# MINI_SAM_D51_012.net
KiCad netlist of a schematic drawn in EAGLE
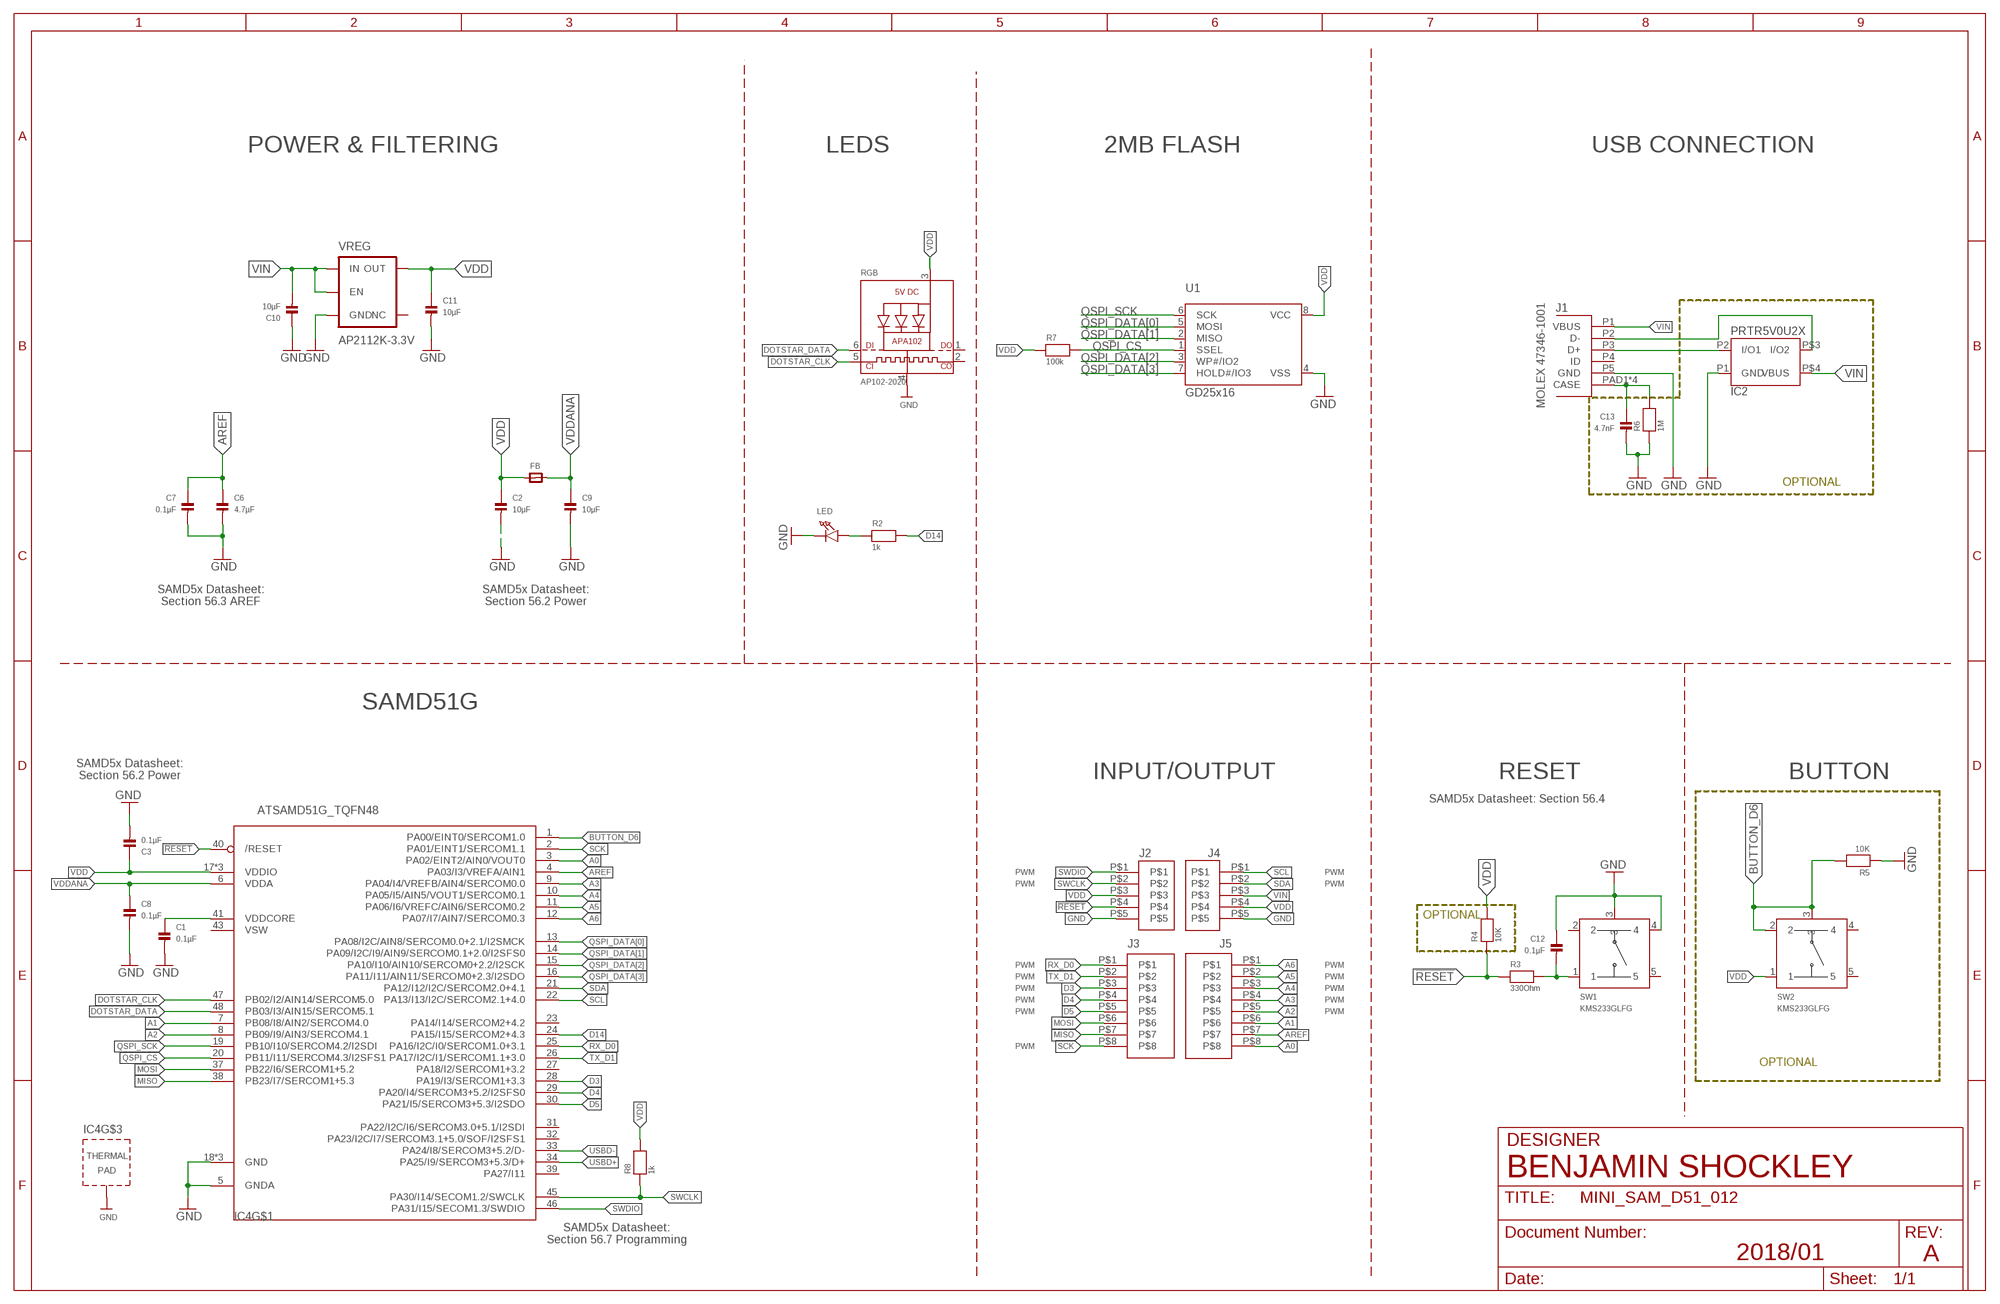
[diagram p0: schematic, sheet 1]

(export (version "E")
  (design (tool "Eeschema 10.0.6"))
  (components
    (comp (ref "C1")
      (value "0.1µF")
      (footprint "eagle-import:_0603MP")
      (libsource (lib "eagle-import") (part "CAP_CERAMIC_0603MP"))
    )
    (comp (ref "C2")
      (value "10µF")
      (footprint "eagle-import:_0603MP")
      (libsource (lib "eagle-import") (part "CAP_CERAMIC_0603MP"))
    )
    (comp (ref "C3")
      (value "0.1µF")
      (footprint "eagle-import:_0603MP")
      (libsource (lib "eagle-import") (part "CAP_CERAMIC_0603MP"))
    )
    (comp (ref "C6")
      (value "4.7µF")
      (footprint "eagle-import:_0603MP")
      (libsource (lib "eagle-import") (part "CAP_CERAMIC_0603MP"))
    )
    (comp (ref "C7")
      (value "0.1µF")
      (footprint "eagle-import:_0603MP")
      (libsource (lib "eagle-import") (part "CAP_CERAMIC_0603MP"))
    )
    (comp (ref "C8")
      (value "0.1µF")
      (footprint "eagle-import:_0603MP")
      (libsource (lib "eagle-import") (part "CAP_CERAMIC_0603MP"))
    )
    (comp (ref "C9")
      (value "10µF")
      (footprint "eagle-import:_0603MP")
      (libsource (lib "eagle-import") (part "CAP_CERAMIC_0603MP"))
    )
    (comp (ref "C10")
      (value "10µF")
      (footprint "eagle-import:_0603MP")
      (libsource (lib "eagle-import") (part "CAP_CERAMIC_0603MP"))
    )
    (comp (ref "C11")
      (value "10µF")
      (footprint "eagle-import:_0603MP")
      (libsource (lib "eagle-import") (part "CAP_CERAMIC_0603MP"))
    )
    (comp (ref "C12")
      (value "0.1µF")
      (footprint "eagle-import:_0603MP")
      (libsource (lib "eagle-import") (part "CAP_CERAMIC_0603MP"))
    )
    (comp (ref "C13")
      (value "4.7nF")
      (footprint "eagle-import:_0603MP")
      (libsource (lib "eagle-import") (part "CAP_CERAMIC_0603MP"))
    )
    (comp (ref "FB")
      (value "FERRITE_0603MP")
      (footprint "eagle-import:_0603MP")
      (libsource (lib "eagle-import") (part "FERRITE_0603MP"))
    )
    (comp (ref "IC2")
      (value "PRTR5V0U2X")
      (footprint "eagle-import:SOT143B_REFLOW")
      (libsource (lib "eagle-import") (part "PRTR5V0U2X"))
    )
    (comp (ref "IC4")
      (value "ATSAMD51G_TQFN48")
      (footprint "eagle-import:TQFN48_7MM")
      (libsource (lib "eagle-import") (part "ATSAMD51G_TQFN48"))
    )
    (comp (ref "J1")
      (value "MOLEX_47346-100147346")
      (footprint "eagle-import:MOLEX_47346-1001")
      (libsource (lib "eagle-import") (part "MOLEX_47346-100147346"))
    )
    (comp (ref "J2")
      (value "1X5_HEADER_1.27MM")
      (footprint "eagle-import:1X5_HEADER_1.27MM")
      (libsource (lib "eagle-import") (part "1X5_HEADER_1.27MM"))
    )
    (comp (ref "J3")
      (value "1X8_HEADER_1.27MM")
      (footprint "eagle-import:1X8_HEADER_1.27MM")
      (libsource (lib "eagle-import") (part "1X8_HEADER_1.27MM"))
    )
    (comp (ref "J4")
      (value "1X5_HEADER_1.27MM")
      (footprint "eagle-import:1X5_HEADER_1.27MM")
      (libsource (lib "eagle-import") (part "1X5_HEADER_1.27MM"))
    )
    (comp (ref "J5")
      (value "1X8_HEADER_1.27MM")
      (footprint "eagle-import:1X8_HEADER_1.27MM")
      (libsource (lib "eagle-import") (part "1X8_HEADER_1.27MM"))
    )
    (comp (ref "LED")
      (value "LED0805_NOOUTLINE")
      (footprint "eagle-import:CHIPLED_0805_NOOUTLINE")
      (libsource (lib "eagle-import") (part "LED0805_NOOUTLINE"))
    )
    (comp (ref "R2")
      (value "1k")
      (footprint "eagle-import:_0603MP")
      (libsource (lib "eagle-import") (part "RESISTOR_0603MP"))
    )
    (comp (ref "R3")
      (value "330Ohm")
      (footprint "eagle-import:_0603MP")
      (libsource (lib "eagle-import") (part "RESISTOR_0603MP"))
    )
    (comp (ref "R4")
      (value "10K")
      (footprint "eagle-import:_0603MP")
      (libsource (lib "eagle-import") (part "RESISTOR_0603MP"))
    )
    (comp (ref "R5")
      (value "10K")
      (footprint "eagle-import:_0603MP")
      (libsource (lib "eagle-import") (part "RESISTOR_0603MP"))
    )
    (comp (ref "R6")
      (value "1M")
      (footprint "eagle-import:_0603MP")
      (libsource (lib "eagle-import") (part "RESISTOR_0603MP"))
    )
    (comp (ref "R7")
      (value "100k")
      (footprint "eagle-import:_0603MP")
      (libsource (lib "eagle-import") (part "RESISTOR_0603MP"))
    )
    (comp (ref "R8")
      (value "1k")
      (footprint "eagle-import:_0603MP")
      (libsource (lib "eagle-import") (part "RESISTOR_0603MP"))
    )
    (comp (ref "RGB")
      (value "AP102-2020")
      (footprint "eagle-import:APA102_2020")
      (libsource (lib "eagle-import") (part "APA1022020"))
    )
    (comp (ref "SW1")
      (value "KMS233GLFG")
      (footprint "eagle-import:KMS_SWITCH")
      (libsource (lib "eagle-import") (part "KMS_SWITCHKMS"))
    )
    (comp (ref "SW2")
      (value "KMS233GLFG")
      (footprint "eagle-import:KMS_SWITCH")
      (libsource (lib "eagle-import") (part "KMS_SWITCHKMS"))
    )
    (comp (ref "U1")
      (value "GD25x16")
      (footprint "eagle-import:USON8")
      (libsource (lib "eagle-import") (part "SPIFLASH_8PINUX"))
    )
    (comp (ref "VREG")
      (value "AP2112K-3.3V")
      (footprint "eagle-import:SOT23-5")
      (libsource (lib "eagle-import") (part "V_REG_AP2112K-3.3V"))
    )
  )
  (nets
    (net (code "1") (name "/VSW") (class "Default")
      (node (ref "IC4") (pin "43") (pinfunction "VSW_43") (pintype "power_in"))
    )
    (net (code "2") (name "/~{RESET}") (class "Default")
      (node (ref "IC4") (pin "40") (pinfunction "/RESET_40") (pintype "bidirectional"))
      (node (ref "J2") (pin "P$4") (pinfunction "P$4_P$4") (pintype "bidirectional"))
      (node (ref "R3") (pin "1") (pinfunction "1_1") (pintype "passive"))
      (node (ref "R4") (pin "1") (pinfunction "1_1") (pintype "passive"))
    )
    (net (code "3") (name "A0") (class "Default")
      (node (ref "IC4") (pin "3") (pinfunction "PA02/EINT2/AIN0/VOUT0_3") (pintype "bidirectional"))
      (node (ref "J5") (pin "P$8") (pinfunction "P$8_P$8") (pintype "bidirectional"))
    )
    (net (code "4") (name "A1") (class "Default")
      (node (ref "IC4") (pin "7") (pinfunction "PB08/I8/AIN2/SERCOM4.0_7") (pintype "bidirectional"))
      (node (ref "J5") (pin "P$6") (pinfunction "P$6_P$6") (pintype "bidirectional"))
    )
    (net (code "5") (name "A2") (class "Default")
      (node (ref "IC4") (pin "8") (pinfunction "PB09/I9/AIN3/SERCOM4.1_8") (pintype "bidirectional"))
      (node (ref "J5") (pin "P$5") (pinfunction "P$5_P$5") (pintype "bidirectional"))
    )
    (net (code "6") (name "A3") (class "Default")
      (node (ref "IC4") (pin "9") (pinfunction "PA04/I4/VREFB/AIN4/SERCOM0.0_9") (pintype "bidirectional"))
      (node (ref "J5") (pin "P$4") (pinfunction "P$4_P$4") (pintype "bidirectional"))
    )
    (net (code "7") (name "A4") (class "Default")
      (node (ref "IC4") (pin "10") (pinfunction "PA05/I5/AIN5/VOUT1/SERCOM0.1_10") (pintype "bidirectional"))
      (node (ref "J5") (pin "P$3") (pinfunction "P$3_P$3") (pintype "bidirectional"))
    )
    (net (code "8") (name "A5") (class "Default")
      (node (ref "IC4") (pin "11") (pinfunction "PA06/I6/VREFC/AIN6/SERCOM0.2_11") (pintype "bidirectional"))
      (node (ref "J5") (pin "P$2") (pinfunction "P$2_P$2") (pintype "bidirectional"))
    )
    (net (code "9") (name "A6") (class "Default")
      (node (ref "IC4") (pin "12") (pinfunction "PA07/I7/AIN7/SERCOM0.3_12") (pintype "bidirectional"))
      (node (ref "J5") (pin "P$1") (pinfunction "P$1_P$1") (pintype "bidirectional"))
    )
    (net (code "10") (name "AREF") (class "Default")
      (node (ref "C6") (pin "1") (pinfunction "P$1_1") (pintype "passive"))
      (node (ref "C7") (pin "1") (pinfunction "P$1_1") (pintype "passive"))
      (node (ref "IC4") (pin "4") (pinfunction "PA03/I3/VREFA/AIN1_4") (pintype "bidirectional"))
      (node (ref "J5") (pin "P$7") (pinfunction "P$7_P$7") (pintype "bidirectional"))
    )
    (net (code "11") (name "BUTTON_D6") (class "Default")
      (node (ref "IC4") (pin "1") (pinfunction "PA00/EINT0/SERCOM1.0_1") (pintype "bidirectional"))
      (node (ref "R5") (pin "2") (pinfunction "2_2") (pintype "passive"))
      (node (ref "SW2") (pin "2") (pinfunction "2_2") (pintype "bidirectional"))
      (node (ref "SW2") (pin "3") (pinfunction "3_3") (pintype "bidirectional"))
    )
    (net (code "12") (name "D3") (class "Default")
      (node (ref "IC4") (pin "28") (pinfunction "PA19/I3/SERCOM1+3.3_28") (pintype "bidirectional"))
      (node (ref "J3") (pin "P$3") (pinfunction "P$3_P$3") (pintype "bidirectional"))
    )
    (net (code "13") (name "D4") (class "Default")
      (node (ref "IC4") (pin "29") (pinfunction "PA20/I4/SERCOM3+5.2/I2SFS0_29") (pintype "bidirectional"))
      (node (ref "J3") (pin "P$4") (pinfunction "P$4_P$4") (pintype "bidirectional"))
    )
    (net (code "14") (name "D5") (class "Default")
      (node (ref "IC4") (pin "30") (pinfunction "PA21/I5/SERCOM3+5.3/I2SDO_30") (pintype "bidirectional"))
      (node (ref "J3") (pin "P$5") (pinfunction "P$5_P$5") (pintype "bidirectional"))
    )
    (net (code "15") (name "D14") (class "Default")
      (node (ref "IC4") (pin "24") (pinfunction "PA15/I15/SERCOM2+4.3_24") (pintype "bidirectional"))
      (node (ref "R2") (pin "2") (pinfunction "2_2") (pintype "passive"))
    )
    (net (code "16") (name "DOTSTAR_CLK") (class "Default")
      (node (ref "IC4") (pin "47") (pinfunction "PB02/I2/AIN14/SERCOM5.0_47") (pintype "bidirectional"))
      (node (ref "RGB") (pin "5") (pinfunction "CKI_5") (pintype "input"))
    )
    (net (code "17") (name "DOTSTAR_DATA") (class "Default")
      (node (ref "IC4") (pin "48") (pinfunction "PB03/I3/AIN15/SERCOM5.1_48") (pintype "bidirectional"))
      (node (ref "RGB") (pin "6") (pinfunction "DI_6") (pintype "input"))
    )
    (net (code "18") (name "GND") (class "Default")
      (node (ref "C1") (pin "2") (pinfunction "P$2_2") (pintype "passive"))
      (node (ref "C10") (pin "1") (pinfunction "P$1_1") (pintype "passive"))
      (node (ref "C11") (pin "2") (pinfunction "P$2_2") (pintype "passive"))
      (node (ref "C12") (pin "1") (pinfunction "P$1_1") (pintype "passive"))
      (node (ref "C13") (pin "2") (pinfunction "P$2_2") (pintype "passive"))
      (node (ref "C2") (pin "2") (pinfunction "P$2_2") (pintype "passive"))
      (node (ref "C3") (pin "2") (pinfunction "P$2_2") (pintype "passive"))
      (node (ref "C6") (pin "2") (pinfunction "P$2_2") (pintype "passive"))
      (node (ref "C7") (pin "2") (pinfunction "P$2_2") (pintype "passive"))
      (node (ref "C8") (pin "2") (pinfunction "P$2_2") (pintype "passive"))
      (node (ref "C9") (pin "2") (pinfunction "P$2_2") (pintype "passive"))
      (node (ref "IC2") (pin "P1") (pinfunction "GND_P1") (pintype "bidirectional"))
      (node (ref "IC4") (pin "18") (pinfunction "GND_18") (pintype "power_in"))
      (node (ref "IC4") (pin "35") (pinfunction "GND_35") (pintype "power_in"))
      (node (ref "IC4") (pin "42") (pinfunction "GND_42") (pintype "power_in"))
      (node (ref "IC4") (pin "5") (pinfunction "GNDA_5") (pintype "power_in"))
      (node (ref "IC4") (pin "THERMAL") (pinfunction "TP_THERMAL") (pintype "power_in"))
      (node (ref "J1") (pin "P5") (pinfunction "GND_P5") (pintype "power_in"))
      (node (ref "J2") (pin "P$5") (pinfunction "P$5_P$5") (pintype "bidirectional"))
      (node (ref "J4") (pin "P$5") (pinfunction "P$5_P$5") (pintype "bidirectional"))
      (node (ref "LED") (pin "C") (pinfunction "C_C") (pintype "passive"))
      (node (ref "R5") (pin "1") (pinfunction "1_1") (pintype "passive"))
      (node (ref "R6") (pin "1") (pinfunction "1_1") (pintype "passive"))
      (node (ref "RGB") (pin "4") (pinfunction "GND_4") (pintype "power_in"))
      (node (ref "SW1") (pin "3") (pinfunction "3_3") (pintype "bidirectional"))
      (node (ref "SW1") (pin "4") (pinfunction "4_4") (pintype "bidirectional"))
      (node (ref "U1") (pin "4") (pinfunction "VSS_4") (pintype "bidirectional"))
      (node (ref "VREG") (pin "2") (pinfunction "GND_2") (pintype "input"))
    )
    (net (code "19") (name "MISO") (class "Default")
      (node (ref "IC4") (pin "38") (pinfunction "PB23/I7/SERCOM1+5.3_38") (pintype "bidirectional"))
      (node (ref "J3") (pin "P$7") (pinfunction "P$7_P$7") (pintype "bidirectional"))
    )
    (net (code "20") (name "MOSI") (class "Default")
      (node (ref "IC4") (pin "37") (pinfunction "PB22/I6/SERCOM1+5.2_37") (pintype "bidirectional"))
      (node (ref "J3") (pin "P$6") (pinfunction "P$6_P$6") (pintype "bidirectional"))
    )
    (net (code "21") (name "Net-(C1-P$1)") (class "Default")
      (node (ref "C1") (pin "1") (pinfunction "P$1_1") (pintype "passive"))
      (node (ref "IC4") (pin "41") (pinfunction "VDDCORE_41") (pintype "power_in"))
    )
    (net (code "22") (name "Net-(C12-P$2)") (class "Default")
      (node (ref "C12") (pin "2") (pinfunction "P$2_2") (pintype "passive"))
      (node (ref "R3") (pin "2") (pinfunction "2_2") (pintype "passive"))
      (node (ref "SW1") (pin "1") (pinfunction "1_1") (pintype "bidirectional"))
    )
    (net (code "23") (name "Net-(C13-P$1)") (class "Default")
      (node (ref "C13") (pin "1") (pinfunction "P$1_1") (pintype "passive"))
      (node (ref "J1") (pin "PAD1") (pinfunction "CASE_PAD1") (pintype "bidirectional"))
      (node (ref "J1") (pin "PAD2") (pinfunction "CASE_PAD2") (pintype "bidirectional"))
      (node (ref "J1") (pin "PAD3") (pinfunction "CASE_PAD3") (pintype "bidirectional"))
      (node (ref "J1") (pin "PAD4") (pinfunction "CASE_PAD4") (pintype "bidirectional"))
      (node (ref "R6") (pin "2") (pinfunction "2_2") (pintype "passive"))
    )
    (net (code "24") (name "Net-(LED-PadA)") (class "Default")
      (node (ref "LED") (pin "A") (pinfunction "A_A") (pintype "passive"))
      (node (ref "R2") (pin "1") (pinfunction "1_1") (pintype "passive"))
    )
    (net (code "25") (name "QSPI_CS") (class "Default")
      (node (ref "IC4") (pin "20") (pinfunction "PB11/I11/SERCOM4.3/I2SFS1_20") (pintype "bidirectional"))
      (node (ref "R7") (pin "2") (pinfunction "2_2") (pintype "passive"))
      (node (ref "U1") (pin "1") (pinfunction "SSEL_1") (pintype "bidirectional"))
    )
    (net (code "26") (name "QSPI_DATA[0]") (class "Default")
      (node (ref "IC4") (pin "13") (pinfunction "PA08/I2C/AIN8/SERCOM0.0+2.1/I2SMCK_13") (pintype "bidirectional"))
      (node (ref "U1") (pin "5") (pinfunction "MOSI_5") (pintype "bidirectional"))
    )
    (net (code "27") (name "QSPI_DATA[1]") (class "Default")
      (node (ref "IC4") (pin "14") (pinfunction "PA09/I2C/I9/AIN9/SERCOM0.1+2.0/I2SFS0_14") (pintype "bidirectional"))
      (node (ref "U1") (pin "2") (pinfunction "MISO_2") (pintype "bidirectional"))
    )
    (net (code "28") (name "QSPI_DATA[2]") (class "Default")
      (node (ref "IC4") (pin "15") (pinfunction "PA10/I10/AIN10/SERCOM0+2.2/I2SCK_15") (pintype "bidirectional"))
      (node (ref "U1") (pin "3") (pinfunction "WP#/IO2_3") (pintype "bidirectional"))
    )
    (net (code "29") (name "QSPI_DATA[3]") (class "Default")
      (node (ref "IC4") (pin "16") (pinfunction "PA11/I11/AIN11/SERCOM0+2.3/I2SDO_16") (pintype "bidirectional"))
      (node (ref "U1") (pin "7") (pinfunction "HOLD#/IO3_7") (pintype "bidirectional"))
    )
    (net (code "30") (name "QSPI_SCK") (class "Default")
      (node (ref "IC4") (pin "19") (pinfunction "PB10/I10/SERCOM4.2/I2SDI_19") (pintype "bidirectional"))
      (node (ref "U1") (pin "6") (pinfunction "SCK_6") (pintype "bidirectional"))
    )
    (net (code "31") (name "RX_D0") (class "Default")
      (node (ref "IC4") (pin "25") (pinfunction "PA16/I2C/I0/SERCOM1.0+3.1_25") (pintype "bidirectional"))
      (node (ref "J3") (pin "P$1") (pinfunction "P$1_P$1") (pintype "bidirectional"))
    )
    (net (code "32") (name "SCK") (class "Default")
      (node (ref "IC4") (pin "2") (pinfunction "PA01/EINT1/SERCOM1.1_2") (pintype "bidirectional"))
      (node (ref "J3") (pin "P$8") (pinfunction "P$8_P$8") (pintype "bidirectional"))
    )
    (net (code "33") (name "SCL") (class "Default")
      (node (ref "IC4") (pin "22") (pinfunction "PA13/I13/I2C/SERCOM2.1+4.0_22") (pintype "bidirectional"))
      (node (ref "J4") (pin "P$1") (pinfunction "P$1_P$1") (pintype "bidirectional"))
    )
    (net (code "34") (name "SDA") (class "Default")
      (node (ref "IC4") (pin "21") (pinfunction "PA12/I12/I2C/SERCOM2.0+4.1_21") (pintype "bidirectional"))
      (node (ref "J4") (pin "P$2") (pinfunction "P$2_P$2") (pintype "bidirectional"))
    )
    (net (code "35") (name "SWCLK") (class "Default")
      (node (ref "IC4") (pin "45") (pinfunction "PA30/I14/SECOM1.2/SWCLK_45") (pintype "bidirectional"))
      (node (ref "J2") (pin "P$2") (pinfunction "P$2_P$2") (pintype "bidirectional"))
      (node (ref "R8") (pin "1") (pinfunction "1_1") (pintype "passive"))
    )
    (net (code "36") (name "SWDIO") (class "Default")
      (node (ref "IC4") (pin "46") (pinfunction "PA31/I15/SECOM1.3/SWDIO_46") (pintype "bidirectional"))
      (node (ref "J2") (pin "P$1") (pinfunction "P$1_P$1") (pintype "bidirectional"))
    )
    (net (code "37") (name "TX_D1") (class "Default")
      (node (ref "IC4") (pin "26") (pinfunction "PA17/I2C/I1/SERCOM1.1+3.0_26") (pintype "bidirectional"))
      (node (ref "J3") (pin "P$2") (pinfunction "P$2_P$2") (pintype "bidirectional"))
    )
    (net (code "38") (name "USBD+") (class "Default")
      (node (ref "IC2") (pin "P2") (pinfunction "I/O1_P2") (pintype "bidirectional"))
      (node (ref "IC4") (pin "34") (pinfunction "PA25/I9/SERCOM3+5.3/D+_34") (pintype "bidirectional"))
      (node (ref "J1") (pin "P3") (pinfunction "D+_P3") (pintype "bidirectional"))
    )
    (net (code "39") (name "USBD-") (class "Default")
      (node (ref "IC2") (pin "P$3") (pinfunction "I/O2_P$3") (pintype "bidirectional"))
      (node (ref "IC4") (pin "33") (pinfunction "PA24/I8/SERCOM3+5.2/D-_33") (pintype "bidirectional"))
      (node (ref "J1") (pin "P2") (pinfunction "D-_P2") (pintype "bidirectional"))
    )
    (net (code "40") (name "VDD") (class "Default")
      (node (ref "C11") (pin "1") (pinfunction "P$1_1") (pintype "passive"))
      (node (ref "C2") (pin "1") (pinfunction "P$1_1") (pintype "passive"))
      (node (ref "C3") (pin "1") (pinfunction "P$1_1") (pintype "passive"))
      (node (ref "FB") (pin "1") (pinfunction "P$1_1") (pintype "passive"))
      (node (ref "IC4") (pin "17") (pinfunction "VDDIO_17") (pintype "power_in"))
      (node (ref "IC4") (pin "36") (pinfunction "VDDIO_36") (pintype "power_in"))
      (node (ref "IC4") (pin "44") (pinfunction "VDDIO_44") (pintype "power_in"))
      (node (ref "J2") (pin "P$3") (pinfunction "P$3_P$3") (pintype "bidirectional"))
      (node (ref "J4") (pin "P$4") (pinfunction "P$4_P$4") (pintype "bidirectional"))
      (node (ref "R4") (pin "2") (pinfunction "2_2") (pintype "passive"))
      (node (ref "R7") (pin "1") (pinfunction "1_1") (pintype "passive"))
      (node (ref "R8") (pin "2") (pinfunction "2_2") (pintype "passive"))
      (node (ref "RGB") (pin "3") (pinfunction "VDD_3") (pintype "power_in"))
      (node (ref "SW2") (pin "1") (pinfunction "1_1") (pintype "bidirectional"))
      (node (ref "U1") (pin "8") (pinfunction "VCC_8") (pintype "bidirectional"))
      (node (ref "VREG") (pin "5") (pinfunction "OUT_5") (pintype "passive"))
    )
    (net (code "41") (name "VDDANA") (class "Default")
      (node (ref "C8") (pin "1") (pinfunction "P$1_1") (pintype "passive"))
      (node (ref "C9") (pin "1") (pinfunction "P$1_1") (pintype "passive"))
      (node (ref "FB") (pin "2") (pinfunction "P$2_2") (pintype "passive"))
      (node (ref "IC4") (pin "6") (pinfunction "VDDA_6") (pintype "power_in"))
    )
    (net (code "42") (name "VIN") (class "Default")
      (node (ref "C10") (pin "2") (pinfunction "P$2_2") (pintype "passive"))
      (node (ref "IC2") (pin "P$4") (pinfunction "VBUS_P$4") (pintype "bidirectional"))
      (node (ref "J1") (pin "P1") (pinfunction "VBUS_P1") (pintype "power_in"))
      (node (ref "J4") (pin "P$3") (pinfunction "P$3_P$3") (pintype "bidirectional"))
      (node (ref "VREG") (pin "1") (pinfunction "IN_1") (pintype "input"))
      (node (ref "VREG") (pin "3") (pinfunction "EN_3") (pintype "input"))
    )
    (net (code "43") (name "unconnected-(IC4A-PA14{slash}I14{slash}SERCOM2+4.2-Pad23)") (class "Default")
      (node (ref "IC4") (pin "23") (pinfunction "PA14/I14/SERCOM2+4.2_23") (pintype "bidirectional"))
    )
    (net (code "44") (name "unconnected-(IC4A-PA18{slash}I2{slash}SERCOM1+3.2-Pad27)") (class "Default")
      (node (ref "IC4") (pin "27") (pinfunction "PA18/I2/SERCOM1+3.2_27") (pintype "bidirectional"))
    )
    (net (code "45") (name "unconnected-(IC4A-PA22{slash}I2C{slash}I6{slash}SERCOM3.0+5.1{slash}I2SDI-Pad31)") (class "Default")
      (node (ref "IC4") (pin "31") (pinfunction "PA22/I2C/I6/SERCOM3.0+5.1/I2SDI_31") (pintype "bidirectional"))
    )
    (net (code "46") (name "unconnected-(IC4A-PA23{slash}I2C{slash}I7{slash}SERCOM3.1+5.0{slash}SOF{slash}I2SFS1-Pad32)") (class "Default")
      (node (ref "IC4") (pin "32") (pinfunction "PA23/I2C/I7/SERCOM3.1+5.0/SOF/I2SFS1_32") (pintype "bidirectional"))
    )
    (net (code "47") (name "unconnected-(IC4A-PA27{slash}I11-Pad39)") (class "Default")
      (node (ref "IC4") (pin "39") (pinfunction "PA27/I11_39") (pintype "bidirectional"))
    )
    (net (code "48") (name "unconnected-(J1-ID-PadP4)") (class "Default")
      (node (ref "J1") (pin "P4") (pinfunction "ID_P4") (pintype "bidirectional"))
    )
    (net (code "49") (name "unconnected-(RGB-CKO-Pad2)") (class "Default")
      (node (ref "RGB") (pin "2") (pinfunction "CKO_2") (pintype "output"))
    )
    (net (code "50") (name "unconnected-(RGB-DO-Pad1)") (class "Default")
      (node (ref "RGB") (pin "1") (pinfunction "DO_1") (pintype "output"))
    )
    (net (code "51") (name "unconnected-(SW1-Pad2)") (class "Default")
      (node (ref "SW1") (pin "2") (pinfunction "2_2") (pintype "bidirectional"))
    )
    (net (code "52") (name "unconnected-(SW1-Pad5)") (class "Default")
      (node (ref "SW1") (pin "5") (pinfunction "5_5") (pintype "bidirectional"))
    )
    (net (code "53") (name "unconnected-(SW2-Pad4)") (class "Default")
      (node (ref "SW2") (pin "4") (pinfunction "4_4") (pintype "bidirectional"))
    )
    (net (code "54") (name "unconnected-(SW2-Pad5)") (class "Default")
      (node (ref "SW2") (pin "5") (pinfunction "5_5") (pintype "bidirectional"))
    )
    (net (code "55") (name "unconnected-(VREG-NC-Pad4)") (class "Default")
      (node (ref "VREG") (pin "4") (pinfunction "NC_4") (pintype "input"))
    )
  )
)
